# 04_can.net
KiCad netlist of a schematic drawn in Altium Designer
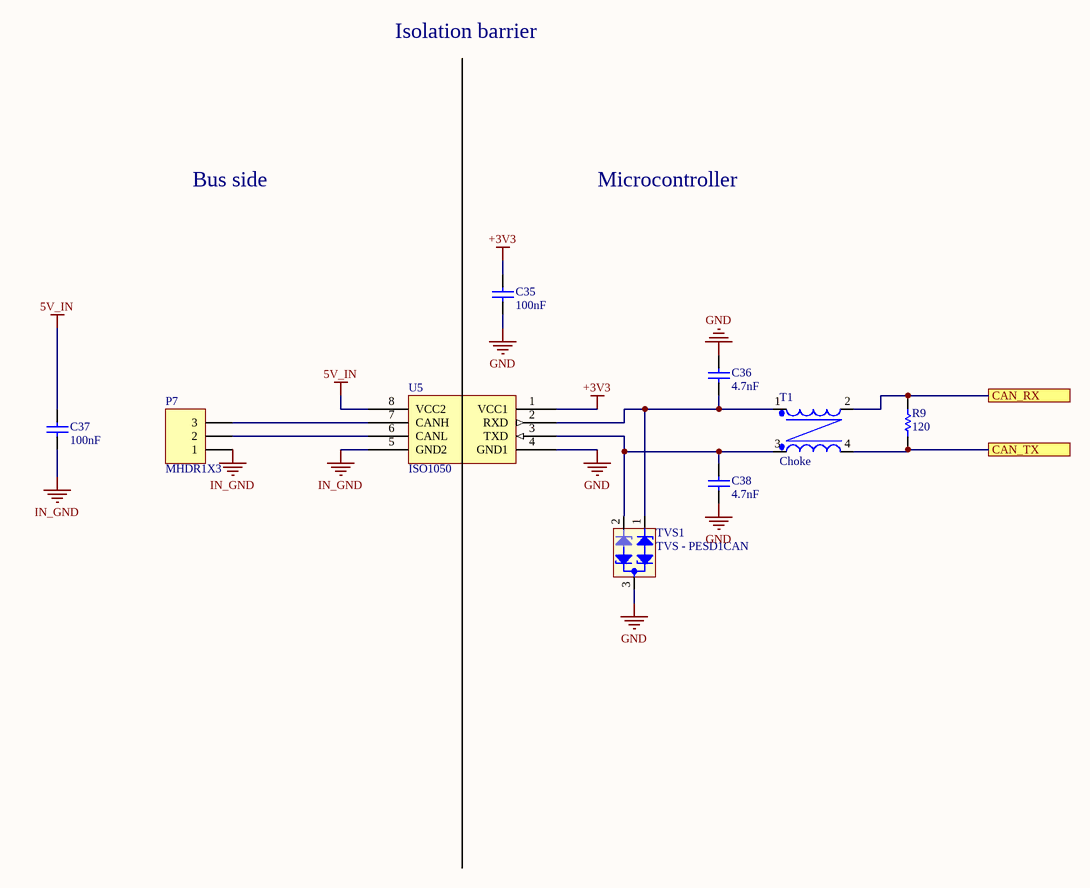
[diagram p0: 04_can.SchDoc]

(export (version "E")
  (design (tool "Eeschema 10.0.6"))
  (components
    (comp (ref "C35")
      (value "100nF")
      (footprint "C0603")
      (description "Capacitor, MLCC, 100nF, 16V, X5R, 10%, 0603, T=0,8mm")
      (fields
        (field (name "INTERNAL_PART_NUMBER") "MCD-00010")
        (field (name "MANUFACTURER_PART_NUMBER") "CC0603KRX5R7BB105")
        (field (name "PROVIDED_BY") "SUBCO")
      )
      (libsource (lib "MCD_PARTS_database") (part "Capacitor"))
    )
    (comp (ref "C36")
      (value "4.7nF")
      (footprint "C0603")
      (description "Capacitor, MLCC, 4.7nF, 16V, X7R, 10%, 0402, T=0,5mm")
      (fields
        (field (name "INTERNAL_PART_NUMBER") "MCD-00102")
        (field (name "MANUFACTURER_PART_NUMBER") "CC0402KRX7R7BB104")
        (field (name "PROVIDED_BY") "SUBCO")
      )
      (libsource (lib "MCD_PARTS_database") (part "Capacitor"))
    )
    (comp (ref "C37")
      (value "100nF")
      (footprint "C0603")
      (description "Capacitor, MLCC, 100nF, 16V, X5R, 10%, 0603, T=0,8mm")
      (fields
        (field (name "INTERNAL_PART_NUMBER") "MCD-00010")
        (field (name "MANUFACTURER_PART_NUMBER") "CC0603KRX5R7BB105")
        (field (name "PROVIDED_BY") "SUBCO")
      )
      (libsource (lib "MCD_PARTS_database") (part "Capacitor"))
    )
    (comp (ref "C38")
      (value "4.7nF")
      (footprint "C0603")
      (description "Capacitor, MLCC, 4.7nF, 16V, X7R, 10%, 0402, T=0,5mm")
      (fields
        (field (name "INTERNAL_PART_NUMBER") "MCD-00102")
        (field (name "MANUFACTURER_PART_NUMBER") "CC0402KRX7R7BB104")
        (field (name "PROVIDED_BY") "SUBCO")
      )
      (libsource (lib "MCD_PARTS_database") (part "Capacitor"))
    )
    (comp (ref "P7")
      (value "MHDR1X3")
      (footprint "MHDR1X3")
      (description "Header, 3-Pin")
      (fields (field (name "PUBLISHER") "Altium Limited"))
      (libsource (lib "Miscellaneous Connectors") (part "MHDR1X3"))
    )
    (comp (ref "R9")
      (value "120")
      (footprint "R0603")
      (description "Resistor,120,0603,1%,1/10W")
      (fields
        (field (name "INTERNAL_PART_NUMBER") "MCD-00220")
        (field (name "MANUFACTURER_PART_NUMBER") "RC0603FR-0710KL")
        (field (name "PROVIDED_BY") "Subcon")
      )
      (libsource (lib "MCD_PARTS_database") (part "Resistor"))
    )
    (comp (ref "T1")
      (value "Choke")
      (footprint "Choke 744232601 Wurth - Footprint Fabricante")
      (description "Choke modo comun")
      (libsource (lib "Project_PIER002.1.1") (part "Choke_1"))
    )
    (comp (ref "TVS1")
      (value "TVS - PESD1CAN")
      (footprint "SOT23A")
      (description "CAN bus ESD protection diode")
      (libsource (lib "Project_PIER002.1.1") (part "TVS - PESD1CAN"))
    )
    (comp (ref "U5")
      (value "ISO1050")
      (footprint "ISO1050")
      (description "CAN Transceiver, Isolated, Vcc1 - 3 to 5V, Vcc2 - 5V")
      (libsource (lib "Project_PIER002.1.1") (part "ISO1050"))
    )
  )
  (nets
    (net (code "1") (name "+3V3") (class "Default")
      (node (ref "C35") (pin "2") (pinfunction "2_2") (pintype "passive"))
      (node (ref "U5") (pin "1") (pinfunction "VCC1_1") (pintype "power_in"))
    )
    (net (code "2") (name "/CAN_RX") (class "Default")
      (node (ref "R9") (pin "1") (pinfunction "1_1") (pintype "passive"))
      (node (ref "T1") (pin "2") (pinfunction "Sec+_2") (pintype "passive"))
    )
    (net (code "3") (name "/CAN_TX") (class "Default")
      (node (ref "R9") (pin "2") (pinfunction "2_2") (pintype "passive"))
      (node (ref "T1") (pin "4") (pinfunction "Sec-_4") (pintype "passive"))
    )
    (net (code "4") (name "5V_IN") (class "Default")
      (node (ref "C37") (pin "2") (pinfunction "2_2") (pintype "passive"))
      (node (ref "U5") (pin "8") (pinfunction "VCC2_8") (pintype "passive"))
    )
    (net (code "5") (name "GND") (class "Default")
      (node (ref "C35") (pin "1") (pinfunction "1_1") (pintype "passive"))
      (node (ref "C36") (pin "2") (pinfunction "2_2") (pintype "passive"))
      (node (ref "C38") (pin "1") (pinfunction "1_1") (pintype "passive"))
      (node (ref "TVS1") (pin "3") (pinfunction "Common_Cathode_3") (pintype "passive"))
      (node (ref "U5") (pin "4") (pinfunction "GND1_4") (pintype "power_in"))
    )
    (net (code "6") (name "IN_GND") (class "Default")
      (node (ref "C37") (pin "1") (pinfunction "1_1") (pintype "passive"))
      (node (ref "P7") (pin "1") (pinfunction "1_1") (pintype "passive"))
      (node (ref "U5") (pin "5") (pinfunction "GND2_5") (pintype "passive"))
    )
    (net (code "7") (name "Net-(T1-Pri+)") (class "Default")
      (node (ref "C36") (pin "1") (pinfunction "1_1") (pintype "passive"))
      (node (ref "T1") (pin "1") (pinfunction "Pri+_1") (pintype "passive"))
      (node (ref "TVS1") (pin "1") (pinfunction "Cathode_1") (pintype "passive"))
      (node (ref "U5") (pin "2") (pinfunction "RXD_2") (pintype "output"))
    )
    (net (code "8") (name "Net-(T1-Pri-)") (class "Default")
      (node (ref "C38") (pin "2") (pinfunction "2_2") (pintype "passive"))
      (node (ref "T1") (pin "3") (pinfunction "Pri-_3") (pintype "passive"))
      (node (ref "TVS1") (pin "2") (pinfunction "Cathode_2") (pintype "passive"))
      (node (ref "U5") (pin "3") (pinfunction "TXD_3") (pintype "input"))
    )
    (net (code "9") (name "Net-(U5-CANH)") (class "Default")
      (node (ref "P7") (pin "3") (pinfunction "3_3") (pintype "passive"))
      (node (ref "U5") (pin "7") (pinfunction "CANH_7") (pintype "passive"))
    )
    (net (code "10") (name "Net-(U5-CANL)") (class "Default")
      (node (ref "P7") (pin "2") (pinfunction "2_2") (pintype "passive"))
      (node (ref "U5") (pin "6") (pinfunction "CANL_6") (pintype "passive"))
    )
  )
)
